# PIC32_Subsystem.net
KiCad netlist of a schematic drawn in Altium Designer
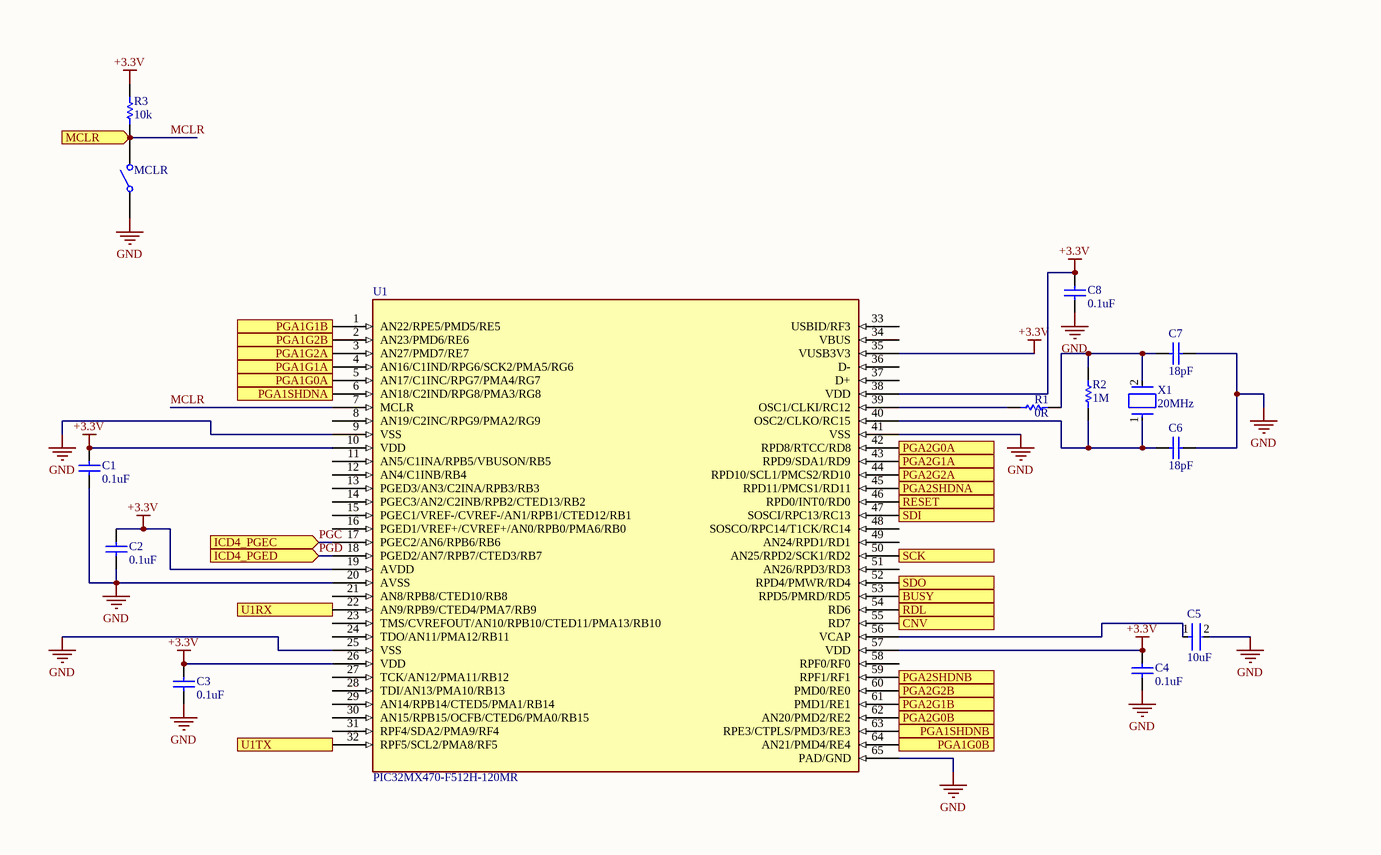
[diagram p0: PIC32_Subsystem.SchDoc, left]

(export (version "E")
  (design (tool "Eeschema 10.0.6"))
  (components
    (comp (ref "C1")
      (value "0.1uF")
      (footprint "CAPC1050X55X23ML05T13")
      (fields (field (name "MANUFACTURER") "Samsung Electro-Mechanics"))
      (libsource (lib "Altium Content Vault") (part "CAP-NP-2"))
    )
    (comp (ref "C2")
      (value "0.1uF")
      (footprint "CAPC1050X55X23ML05T13")
      (fields (field (name "MANUFACTURER") "Samsung Electro-Mechanics"))
      (libsource (lib "Altium Content Vault") (part "CAP-NP-2"))
    )
    (comp (ref "C3")
      (value "0.1uF")
      (footprint "CAPC1050X55X23ML05T13")
      (fields (field (name "MANUFACTURER") "Samsung Electro-Mechanics"))
      (libsource (lib "Altium Content Vault") (part "CAP-NP-2"))
    )
    (comp (ref "C4")
      (value "0.1uF")
      (footprint "CAPC1050X55X23ML05T13")
      (fields (field (name "MANUFACTURER") "Samsung Electro-Mechanics"))
      (libsource (lib "Altium Content Vault") (part "CAP-NP-2"))
    )
    (comp (ref "C5")
      (value "10uF")
      (footprint "FP-GRM188-0_1-e0_2_0_55-IPC_A")
      (fields (field (name "VOLTAGE") "6.3V") (field (name "TOLERANCE") "20%"))
      (libsource (lib "Altium Content Vault") (part "02cd4be3c70576c341d710602a673aa"))
    )
    (comp (ref "C6")
      (value "18pF")
      (footprint "CAPC1005X55X25LL05T10")
      (description "GRM1555C1H180GA01D")
      (fields (field (name "MANUFACTURER") "Murata"))
      (libsource (lib "Altium Content Vault") (part "CAP"))
    )
    (comp (ref "C7")
      (value "18pF")
      (footprint "CAPC1005X55X25LL05T10")
      (description "GRM1555C1H180GA01D")
      (fields (field (name "MANUFACTURER") "Murata"))
      (libsource (lib "Altium Content Vault") (part "CAP"))
    )
    (comp (ref "C8")
      (value "0.1uF")
      (footprint "CAPC1050X55X23ML05T13")
      (fields (field (name "MANUFACTURER") "Samsung Electro-Mechanics"))
      (libsource (lib "Altium Content Vault") (part "CAP-NP-2"))
    )
    (comp (ref "MCLR")
      (value "434121043816")
      (footprint "434121043816")
      (description "WS-TASV SMD Tact Switch 6.0X3.5 mm")
      (fields (field (name "MANUFACTURER") "Wuerth Elektronik"))
      (libsource (lib "Altium Content Vault") (part "WE-TACT-SW-2"))
    )
    (comp (ref "R1")
      (value "0R")
      (footprint "RESC1005X40X25NL05T10")
      (description "RC0402JR-070RL")
      (fields (field (name "MANUFACTURER") "Yageo / Phycomp"))
      (libsource (lib "Altium Content Vault") (part "RES"))
    )
    (comp (ref "R2")
      (value "1M")
      (footprint "RESC1005X40X25LL05T05")
      (fields
        (field (name "PARTNUMBER") "ERJ-2RKF1004X")
        (field (name "TOLERANCE") "1%")
        (field (name "MANUFACTURER") "Basic Passives")
      )
      (libsource (lib "Altium Content Vault") (part "RES-2"))
    )
    (comp (ref "R3")
      (value "10k")
      (footprint "RESC1005X40X25LL05T05")
      (fields (field (name "TOLERANCE") "1%") (field (name "MANUFACTURER") "Panasonic"))
      (libsource (lib "Altium Content Vault") (part "RES-2"))
    )
    (comp (ref "U1")
      (value "PIC32MX470-F512H-120MR")
      (footprint "QFN50P900X900X100-65N")
      (libsource (lib "PIC32MX470-F512H-120MR") (part "PIC32MX470-F512H-120MR"))
    )
    (comp (ref "X1")
      (value "20MHz")
      (footprint "FP-ABM7-MFG")
      (description "Crystal 20MHz ±20ppm 18pF SMD-2 6mm x 3.5mm\r\nABM7-20.000MHZ-D2Y-T")
      (fields (field (name "TOLERANCE") "20ppm"))
      (libsource (lib "Altium Content Vault") (part "c23a69dc6c9e2f18f2079038eb95dd1"))
    )
  )
  (nets
    (net (code "1") (name "+3.3V") (class "Default")
      (node (ref "C1") (pin "2") (pinfunction "2_2") (pintype "passive"))
      (node (ref "C2") (pin "2") (pinfunction "2_2") (pintype "passive"))
      (node (ref "C3") (pin "2") (pinfunction "2_2") (pintype "passive"))
      (node (ref "C4") (pin "2") (pinfunction "2_2") (pintype "passive"))
      (node (ref "C8") (pin "2") (pinfunction "2_2") (pintype "passive"))
      (node (ref "R3") (pin "2") (pinfunction "2_2") (pintype "passive"))
      (node (ref "U1") (pin "10") (pinfunction "VDD_10") (pintype "input"))
      (node (ref "U1") (pin "19") (pinfunction "AVDD_19") (pintype "input"))
      (node (ref "U1") (pin "26") (pinfunction "VDD_26") (pintype "input"))
      (node (ref "U1") (pin "35") (pinfunction "VUSB3V3_35") (pintype "input"))
      (node (ref "U1") (pin "38") (pinfunction "VDD_38") (pintype "input"))
      (node (ref "U1") (pin "57") (pinfunction "VDD_57") (pintype "input"))
    )
    (net (code "2") (name "/BUSY") (class "Default")
      (node (ref "U1") (pin "53") (pinfunction "RPD5/PMRD/RD5_53") (pintype "input"))
    )
    (net (code "3") (name "/CNV") (class "Default")
      (node (ref "U1") (pin "55") (pinfunction "RD7_55") (pintype "input"))
    )
    (net (code "4") (name "/MCLR") (class "Default")
      (node (ref "MCLR") (pin "2") (pinfunction "2_2") (pintype "passive"))
      (node (ref "R3") (pin "1") (pinfunction "1_1") (pintype "passive"))
      (node (ref "U1") (pin "7") (pinfunction "MCLR_7") (pintype "input"))
    )
    (net (code "5") (name "/PGA1G0A") (class "Default")
      (node (ref "U1") (pin "5") (pinfunction "AN17/C1INC/RPG7/PMA4/RG7_5") (pintype "input"))
    )
    (net (code "6") (name "/PGA1G0B") (class "Default")
      (node (ref "U1") (pin "64") (pinfunction "AN21/PMD4/RE4_64") (pintype "input"))
    )
    (net (code "7") (name "/PGA1G1A") (class "Default")
      (node (ref "U1") (pin "4") (pinfunction "AN16/C1IND/RPG6/SCK2/PMA5/RG6_4") (pintype "input"))
    )
    (net (code "8") (name "/PGA1G1B") (class "Default")
      (node (ref "U1") (pin "1") (pinfunction "AN22/RPE5/PMD5/RE5_1") (pintype "input"))
    )
    (net (code "9") (name "/PGA1G2A") (class "Default")
      (node (ref "U1") (pin "3") (pinfunction "AN27/PMD7/RE7_3") (pintype "input"))
    )
    (net (code "10") (name "/PGA1G2B") (class "Default")
      (node (ref "U1") (pin "2") (pinfunction "AN23/PMD6/RE6_2") (pintype "input"))
    )
    (net (code "11") (name "/PGA1SHDNA") (class "Default")
      (node (ref "U1") (pin "6") (pinfunction "AN18/C2IND/RPG8/PMA3/RG8_6") (pintype "input"))
    )
    (net (code "12") (name "/PGA1SHDNB") (class "Default")
      (node (ref "U1") (pin "63") (pinfunction "RPE3/CTPLS/PMD3/RE3_63") (pintype "input"))
    )
    (net (code "13") (name "/PGA2G0A") (class "Default")
      (node (ref "U1") (pin "42") (pinfunction "RPD8/RTCC/RD8_42") (pintype "input"))
    )
    (net (code "14") (name "/PGA2G0B") (class "Default")
      (node (ref "U1") (pin "62") (pinfunction "AN20/PMD2/RE2_62") (pintype "input"))
    )
    (net (code "15") (name "/PGA2G1A") (class "Default")
      (node (ref "U1") (pin "43") (pinfunction "RPD9/SDA1/RD9_43") (pintype "input"))
    )
    (net (code "16") (name "/PGA2G1B") (class "Default")
      (node (ref "U1") (pin "61") (pinfunction "PMD1/RE1_61") (pintype "input"))
    )
    (net (code "17") (name "/PGA2G2A") (class "Default")
      (node (ref "U1") (pin "44") (pinfunction "RPD10/SCL1/PMCS2/RD10_44") (pintype "input"))
    )
    (net (code "18") (name "/PGA2G2B") (class "Default")
      (node (ref "U1") (pin "60") (pinfunction "PMD0/RE0_60") (pintype "input"))
    )
    (net (code "19") (name "/PGA2SHDNA") (class "Default")
      (node (ref "U1") (pin "45") (pinfunction "RPD11/PMCS1/RD11_45") (pintype "input"))
    )
    (net (code "20") (name "/PGA2SHDNB") (class "Default")
      (node (ref "U1") (pin "59") (pinfunction "RPF1/RF1_59") (pintype "input"))
    )
    (net (code "21") (name "/PGC") (class "Default")
      (node (ref "U1") (pin "17") (pinfunction "PGEC2/AN6/RPB6/RB6_17") (pintype "input"))
    )
    (net (code "22") (name "/PGD") (class "Default")
      (node (ref "U1") (pin "18") (pinfunction "PGED2/AN7/RPB7/CTED3/RB7_18") (pintype "input"))
    )
    (net (code "23") (name "/RDL") (class "Default")
      (node (ref "U1") (pin "54") (pinfunction "RD6_54") (pintype "input"))
    )
    (net (code "24") (name "/RESET") (class "Default")
      (node (ref "U1") (pin "46") (pinfunction "RPD0/INT0/RD0_46") (pintype "input"))
    )
    (net (code "25") (name "/SCK") (class "Default")
      (node (ref "U1") (pin "50") (pinfunction "AN25/RPD2/SCK1/RD2_50") (pintype "input"))
    )
    (net (code "26") (name "/SDI") (class "Default")
      (node (ref "U1") (pin "47") (pinfunction "SOSCI/RPC13/RC13_47") (pintype "input"))
    )
    (net (code "27") (name "/SDO") (class "Default")
      (node (ref "U1") (pin "52") (pinfunction "RPD4/PMWR/RD4_52") (pintype "input"))
    )
    (net (code "28") (name "/U1RX") (class "Default")
      (node (ref "U1") (pin "22") (pinfunction "AN9/RPB9/CTED4/PMA7/RB9_22") (pintype "input"))
    )
    (net (code "29") (name "/U1TX") (class "Default")
      (node (ref "U1") (pin "32") (pinfunction "RPF5/SCL2/PMA8/RF5_32") (pintype "input"))
    )
    (net (code "30") (name "GND") (class "Default")
      (node (ref "C1") (pin "1") (pinfunction "1_1") (pintype "passive"))
      (node (ref "C2") (pin "1") (pinfunction "1_1") (pintype "passive"))
      (node (ref "C3") (pin "1") (pinfunction "1_1") (pintype "passive"))
      (node (ref "C4") (pin "1") (pinfunction "1_1") (pintype "passive"))
      (node (ref "C5") (pin "2") (pinfunction "2_2") (pintype "passive"))
      (node (ref "C6") (pin "2") (pinfunction "2_2") (pintype "passive"))
      (node (ref "C7") (pin "2") (pinfunction "2_2") (pintype "passive"))
      (node (ref "C8") (pin "1") (pinfunction "1_1") (pintype "passive"))
      (node (ref "MCLR") (pin "1") (pinfunction "1_1") (pintype "passive"))
      (node (ref "U1") (pin "20") (pinfunction "AVSS_20") (pintype "input"))
      (node (ref "U1") (pin "25") (pinfunction "VSS_25") (pintype "input"))
      (node (ref "U1") (pin "41") (pinfunction "VSS_41") (pintype "input"))
      (node (ref "U1") (pin "65") (pinfunction "PAD/GND_65") (pintype "input"))
      (node (ref "U1") (pin "9") (pinfunction "VSS_9") (pintype "input"))
    )
    (net (code "31") (name "Net-(C7-Pad1)") (class "Default")
      (node (ref "C7") (pin "1") (pinfunction "1_1") (pintype "passive"))
      (node (ref "R1") (pin "2") (pinfunction "2_2") (pintype "passive"))
      (node (ref "R2") (pin "2") (pinfunction "2_2") (pintype "passive"))
      (node (ref "X1") (pin "2") (pinfunction "2_2") (pintype "passive"))
    )
    (net (code "32") (name "Net-(U1-OSC1{slash}CLKI{slash}RC12)") (class "Default")
      (node (ref "R1") (pin "1") (pinfunction "1_1") (pintype "passive"))
      (node (ref "U1") (pin "39") (pinfunction "OSC1/CLKI/RC12_39") (pintype "input"))
    )
    (net (code "33") (name "Net-(U1-OSC2{slash}CLKO{slash}RC15)") (class "Default")
      (node (ref "C6") (pin "1") (pinfunction "1_1") (pintype "passive"))
      (node (ref "R2") (pin "1") (pinfunction "1_1") (pintype "passive"))
      (node (ref "U1") (pin "40") (pinfunction "OSC2/CLKO/RC15_40") (pintype "input"))
      (node (ref "X1") (pin "1") (pinfunction "1_1") (pintype "passive"))
    )
    (net (code "34") (name "Net-(U1-VCAP)") (class "Default")
      (node (ref "C5") (pin "1") (pinfunction "1_1") (pintype "passive"))
      (node (ref "U1") (pin "56") (pinfunction "VCAP_56") (pintype "input"))
    )
    (net (code "35") (name "unconnected-(U1-AN4{slash}C1INB{slash}RB4-Pad12)") (class "Default")
      (node (ref "U1") (pin "12") (pinfunction "AN4/C1INB/RB4_12") (pintype "input"))
    )
    (net (code "36") (name "unconnected-(U1-AN5{slash}C1INA{slash}RPB5{slash}VBUSON{slash}RB5-Pad11)") (class "Default")
      (node (ref "U1") (pin "11") (pinfunction "AN5/C1INA/RPB5/VBUSON/RB5_11") (pintype "input"))
    )
    (net (code "37") (name "unconnected-(U1-AN8{slash}RPB8{slash}CTED10{slash}RB8-Pad21)") (class "Default")
      (node (ref "U1") (pin "21") (pinfunction "AN8/RPB8/CTED10/RB8_21") (pintype "input"))
    )
    (net (code "38") (name "unconnected-(U1-AN14{slash}RPB14{slash}CTED5{slash}PMA1{slash}RB14-Pad29)") (class "Default")
      (node (ref "U1") (pin "29") (pinfunction "AN14/RPB14/CTED5/PMA1/RB14_29") (pintype "input"))
    )
    (net (code "39") (name "unconnected-(U1-AN15{slash}RPB15{slash}OCFB{slash}CTED6{slash}PMA0{slash}RB15-Pad30)") (class "Default")
      (node (ref "U1") (pin "30") (pinfunction "AN15/RPB15/OCFB/CTED6/PMA0/RB15_30") (pintype "input"))
    )
    (net (code "40") (name "unconnected-(U1-AN19{slash}C2INC{slash}RPG9{slash}PMA2{slash}RG9-Pad8)") (class "Default")
      (node (ref "U1") (pin "8") (pinfunction "AN19/C2INC/RPG9/PMA2/RG9_8") (pintype "input"))
    )
    (net (code "41") (name "unconnected-(U1-AN24{slash}RPD1{slash}RD1-Pad49)") (class "Default")
      (node (ref "U1") (pin "49") (pinfunction "AN24/RPD1/RD1_49") (pintype "input"))
    )
    (net (code "42") (name "unconnected-(U1-AN26{slash}RPD3{slash}RD3-Pad51)") (class "Default")
      (node (ref "U1") (pin "51") (pinfunction "AN26/RPD3/RD3_51") (pintype "input"))
    )
    (net (code "43") (name "unconnected-(U1-D+-Pad37)") (class "Default")
      (node (ref "U1") (pin "37") (pinfunction "D+_37") (pintype "input"))
    )
    (net (code "44") (name "unconnected-(U1-D--Pad36)") (class "Default")
      (node (ref "U1") (pin "36") (pinfunction "D-_36") (pintype "input"))
    )
    (net (code "45") (name "unconnected-(U1-PGEC1{slash}VREF-{slash}CVREF-{slash}AN1{slash}RPB1{slash}CTED12{slash}RB1-Pad15)") (class "Default")
      (node (ref "U1") (pin "15") (pinfunction "PGEC1/VREF-/CVREF-/AN1/RPB1/CTED12/RB1_15") (pintype "input"))
    )
    (net (code "46") (name "unconnected-(U1-PGEC3{slash}AN2{slash}C2INB{slash}RPB2{slash}CTED13{slash}RB2-Pad14)") (class "Default")
      (node (ref "U1") (pin "14") (pinfunction "PGEC3/AN2/C2INB/RPB2/CTED13/RB2_14") (pintype "input"))
    )
    (net (code "47") (name "unconnected-(U1-PGED1{slash}VREF+{slash}CVREF+{slash}AN0{slash}RPB0{slash}PMA6{slash}RB0-Pad16)") (class "Default")
      (node (ref "U1") (pin "16") (pinfunction "PGED1/VREF+/CVREF+/AN0/RPB0/PMA6/RB0_16") (pintype "input"))
    )
    (net (code "48") (name "unconnected-(U1-PGED3{slash}AN3{slash}C2INA{slash}RPB3{slash}RB3-Pad13)") (class "Default")
      (node (ref "U1") (pin "13") (pinfunction "PGED3/AN3/C2INA/RPB3/RB3_13") (pintype "input"))
    )
    (net (code "49") (name "unconnected-(U1-RPF0{slash}RF0-Pad58)") (class "Default")
      (node (ref "U1") (pin "58") (pinfunction "RPF0/RF0_58") (pintype "input"))
    )
    (net (code "50") (name "unconnected-(U1-RPF4{slash}SDA2{slash}PMA9{slash}RF4-Pad31)") (class "Default")
      (node (ref "U1") (pin "31") (pinfunction "RPF4/SDA2/PMA9/RF4_31") (pintype "input"))
    )
    (net (code "51") (name "unconnected-(U1-SOSCO{slash}RPC14{slash}T1CK{slash}RC14-Pad48)") (class "Default")
      (node (ref "U1") (pin "48") (pinfunction "SOSCO/RPC14/T1CK/RC14_48") (pintype "input"))
    )
    (net (code "52") (name "unconnected-(U1-TCK{slash}AN12{slash}PMA11{slash}RB12-Pad27)") (class "Default")
      (node (ref "U1") (pin "27") (pinfunction "TCK/AN12/PMA11/RB12_27") (pintype "input"))
    )
    (net (code "53") (name "unconnected-(U1-TDI{slash}AN13{slash}PMA10{slash}RB13-Pad28)") (class "Default")
      (node (ref "U1") (pin "28") (pinfunction "TDI/AN13/PMA10/RB13_28") (pintype "input"))
    )
    (net (code "54") (name "unconnected-(U1-TDO{slash}AN11{slash}PMA12{slash}RB11-Pad24)") (class "Default")
      (node (ref "U1") (pin "24") (pinfunction "TDO/AN11/PMA12/RB11_24") (pintype "input"))
    )
    (net (code "55") (name "unconnected-(U1-TMS{slash}CVREFOUT{slash}AN10{slash}RPB10{slash}CTED11{slash}PMA13{slash}RB10-Pad23)") (class "Default")
      (node (ref "U1") (pin "23") (pinfunction "TMS/CVREFOUT/AN10/RPB10/CTED11/PMA13/RB10_23") (pintype "input"))
    )
    (net (code "56") (name "unconnected-(U1-USBID{slash}RF3-Pad33)") (class "Default")
      (node (ref "U1") (pin "33") (pinfunction "USBID/RF3_33") (pintype "input"))
    )
    (net (code "57") (name "unconnected-(U1-VBUS-Pad34)") (class "Default")
      (node (ref "U1") (pin "34") (pinfunction "VBUS_34") (pintype "input"))
    )
  )
)
